# SilentStepStick-TMC2100_v12.net
KiCad netlist of a schematic drawn in EAGLE
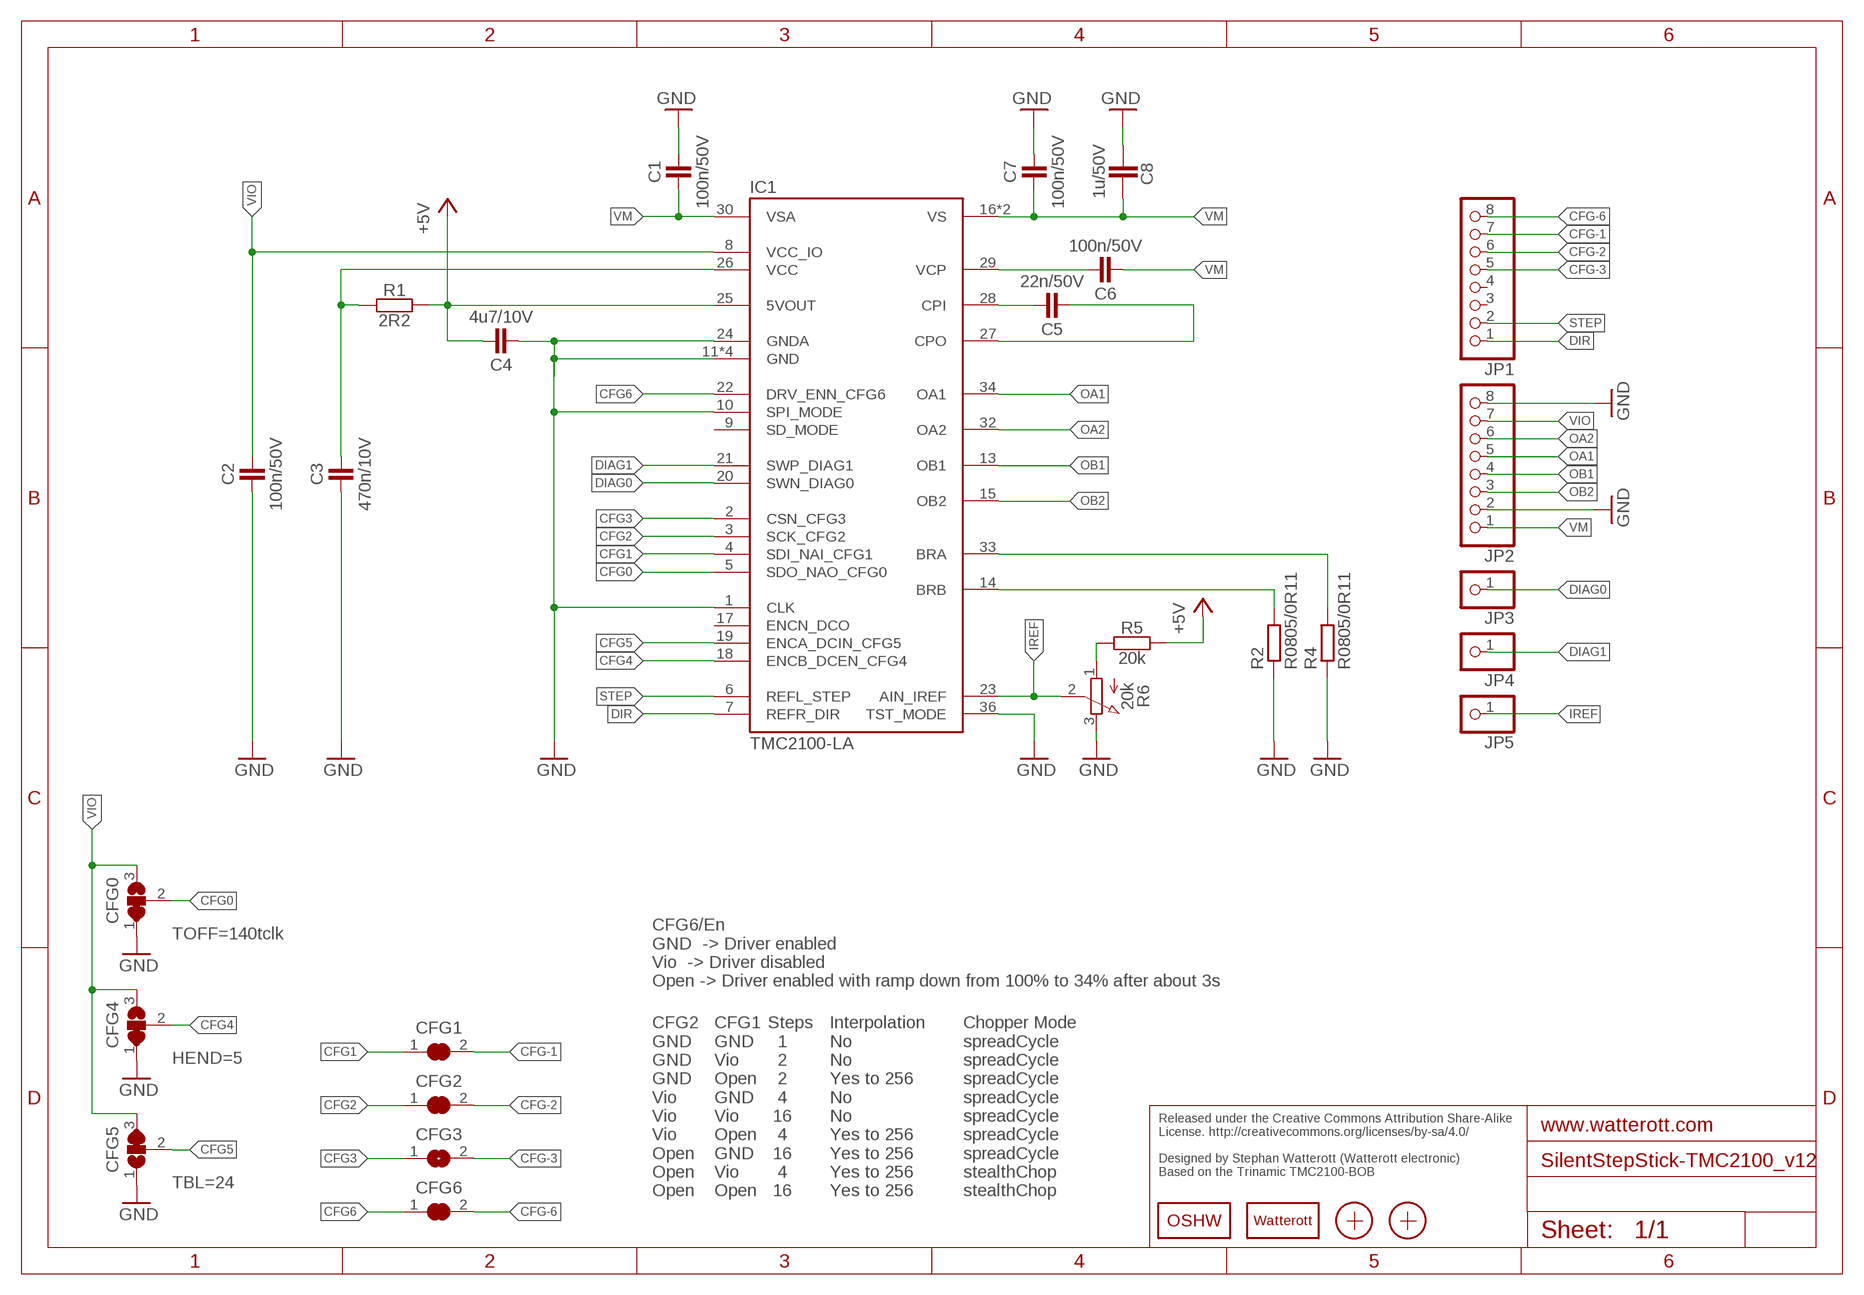
[diagram p0: schematic, sheet 1]

(export (version "E")
  (design (tool "Eeschema 10.0.6"))
  (components
    (comp (ref "C1")
      (value "100n/50V")
      (footprint "eagle-import:C0402")
      (libsource (lib "eagle-import") (part "CAPACITOR-0402"))
    )
    (comp (ref "C2")
      (value "100n/50V")
      (footprint "eagle-import:C0402")
      (libsource (lib "eagle-import") (part "CAPACITOR-0402"))
    )
    (comp (ref "C3")
      (value "470n/10V")
      (footprint "eagle-import:C0402")
      (libsource (lib "eagle-import") (part "CAPACITOR-0402"))
    )
    (comp (ref "C4")
      (value "4u7/10V")
      (footprint "eagle-import:C0402")
      (libsource (lib "eagle-import") (part "CAPACITOR-0402"))
    )
    (comp (ref "C5")
      (value "22n/50V")
      (footprint "eagle-import:C0402")
      (libsource (lib "eagle-import") (part "CAPACITOR-0402"))
    )
    (comp (ref "C6")
      (value "100n/50V")
      (footprint "eagle-import:C0402")
      (libsource (lib "eagle-import") (part "CAPACITOR-0402"))
    )
    (comp (ref "C7")
      (value "100n/50V")
      (footprint "eagle-import:C0402")
      (libsource (lib "eagle-import") (part "CAPACITOR-0402"))
    )
    (comp (ref "C8")
      (value "1u/50V")
      (footprint "eagle-import:C0603")
      (libsource (lib "eagle-import") (part "C-EUC0603"))
    )
    (comp (ref "CFG0")
      (value "JUMPER3-0201")
      (footprint "eagle-import:JUMPER3-0201")
      (libsource (lib "eagle-import") (part "JUMPER3-0201"))
    )
    (comp (ref "CFG1")
      (value "JUMPER2-0201")
      (footprint "eagle-import:JUMPER2-0201")
      (libsource (lib "eagle-import") (part "JUMPER2-0201"))
    )
    (comp (ref "CFG2")
      (value "JUMPER2-0201")
      (footprint "eagle-import:JUMPER2-0201")
      (libsource (lib "eagle-import") (part "JUMPER2-0201"))
    )
    (comp (ref "CFG3")
      (value "JUMPER2-0201")
      (footprint "eagle-import:JUMPER2-0201")
      (libsource (lib "eagle-import") (part "JUMPER2-0201"))
    )
    (comp (ref "CFG4")
      (value "JUMPER3-0201")
      (footprint "eagle-import:JUMPER3-0201")
      (libsource (lib "eagle-import") (part "JUMPER3-0201"))
    )
    (comp (ref "CFG5")
      (value "JUMPER3-0201")
      (footprint "eagle-import:JUMPER3-0201")
      (libsource (lib "eagle-import") (part "JUMPER3-0201"))
    )
    (comp (ref "CFG6")
      (value "JUMPER2-0201")
      (footprint "eagle-import:JUMPER2-0201")
      (libsource (lib "eagle-import") (part "JUMPER2-0201"))
    )
    (comp (ref "IC1")
      (value "TMC2100-LA")
      (footprint "eagle-import:QFN36-PAD")
      (libsource (lib "eagle-import") (part "TMC21X0-LA"))
    )
    (comp (ref "JP1")
      (value "PINHD-1X08_2.54-S")
      (footprint "eagle-import:1X08-S")
      (libsource (lib "eagle-import") (part "PINHD-1X08_2.54-S"))
    )
    (comp (ref "JP2")
      (value "PINHD-1X08_2.54-S")
      (footprint "eagle-import:1X08-S")
      (libsource (lib "eagle-import") (part "PINHD-1X08_2.54-S"))
    )
    (comp (ref "JP3")
      (value "PINHD-1X1")
      (footprint "eagle-import:1X01")
      (libsource (lib "eagle-import") (part "PINHD-1X1"))
    )
    (comp (ref "JP4")
      (value "PINHD-1X1")
      (footprint "eagle-import:1X01")
      (libsource (lib "eagle-import") (part "PINHD-1X1"))
    )
    (comp (ref "JP5")
      (value "PINHD-1X1")
      (footprint "eagle-import:1X01")
      (libsource (lib "eagle-import") (part "PINHD-1X1"))
    )
    (comp (ref "LOGO1")
      (value "OSHW_LOGOX0070")
      (footprint "eagle-import:OSHW_6X70")
      (libsource (lib "eagle-import") (part "OSHW_LOGOX0070"))
    )
    (comp (ref "LOGO2")
      (value "LOGO-S_PLACE_M")
      (footprint "eagle-import:SPARK_TPLACE_M")
      (libsource (lib "eagle-import") (part "LOGO-S_PLACE_M"))
    )
    (comp (ref "R1")
      (value "2R2")
      (footprint "eagle-import:C0402")
      (libsource (lib "eagle-import") (part "RESISTOR-0402"))
    )
    (comp (ref "R2")
      (value "R0805/0R11")
      (footprint "eagle-import:M0805")
      (libsource (lib "eagle-import") (part "R-EU_M0805"))
    )
    (comp (ref "R4")
      (value "R0805/0R11")
      (footprint "eagle-import:M0805")
      (libsource (lib "eagle-import") (part "R-EU_M0805"))
    )
    (comp (ref "R5")
      (value "20k")
      (footprint "eagle-import:C0402")
      (libsource (lib "eagle-import") (part "RESISTOR-0402"))
    )
    (comp (ref "R6")
      (value "20k")
      (footprint "eagle-import:POT_EVM3R")
      (libsource (lib "eagle-import") (part "POTEVM3R"))
    )
    (comp (ref "X1")
      (value "PASSER-07")
      (footprint "eagle-import:PASSER_07MM")
      (libsource (lib "eagle-import") (part "PASSER-07"))
    )
    (comp (ref "X2")
      (value "PASSER-07")
      (footprint "eagle-import:PASSER_07MM")
      (libsource (lib "eagle-import") (part "PASSER-07"))
    )
  )
  (nets
    (net (code "1") (name "+5V") (class "Default")
      (node (ref "C4") (pin "2") (pinfunction "2_2") (pintype "passive"))
      (node (ref "IC1") (pin "25") (pinfunction "5VOUT_25") (pintype "power_in"))
      (node (ref "R1") (pin "2") (pinfunction "2_2") (pintype "passive"))
      (node (ref "R5") (pin "2") (pinfunction "2_2") (pintype "passive"))
    )
    (net (code "2") (name "CFG-1") (class "Default")
      (node (ref "CFG1") (pin "2") (pinfunction "2_2") (pintype "passive"))
      (node (ref "JP1") (pin "7") (pinfunction "7_7") (pintype "passive"))
    )
    (net (code "3") (name "CFG-2") (class "Default")
      (node (ref "CFG2") (pin "2") (pinfunction "2_2") (pintype "passive"))
      (node (ref "JP1") (pin "6") (pinfunction "6_6") (pintype "passive"))
    )
    (net (code "4") (name "CFG-3") (class "Default")
      (node (ref "CFG3") (pin "2") (pinfunction "2_2") (pintype "passive"))
      (node (ref "JP1") (pin "5") (pinfunction "5_5") (pintype "passive"))
    )
    (net (code "5") (name "CFG-6") (class "Default")
      (node (ref "CFG6") (pin "2") (pinfunction "2_2") (pintype "passive"))
      (node (ref "JP1") (pin "8") (pinfunction "8_8") (pintype "passive"))
    )
    (net (code "6") (name "CFG0") (class "Default")
      (node (ref "CFG0") (pin "2") (pinfunction "2_2") (pintype "passive"))
      (node (ref "IC1") (pin "5") (pinfunction "SDO_NAO_CFG0_5") (pintype "bidirectional"))
    )
    (net (code "7") (name "CFG1") (class "Default")
      (node (ref "CFG1") (pin "1") (pinfunction "1_1") (pintype "passive"))
      (node (ref "IC1") (pin "4") (pinfunction "SDI_NAI_CFG1_4") (pintype "bidirectional"))
    )
    (net (code "8") (name "CFG2") (class "Default")
      (node (ref "CFG2") (pin "1") (pinfunction "1_1") (pintype "passive"))
      (node (ref "IC1") (pin "3") (pinfunction "SCK_CFG2_3") (pintype "bidirectional"))
    )
    (net (code "9") (name "CFG3") (class "Default")
      (node (ref "CFG3") (pin "1") (pinfunction "1_1") (pintype "passive"))
      (node (ref "IC1") (pin "2") (pinfunction "CSN_CFG3_2") (pintype "bidirectional"))
    )
    (net (code "10") (name "CFG4") (class "Default")
      (node (ref "CFG4") (pin "2") (pinfunction "2_2") (pintype "passive"))
      (node (ref "IC1") (pin "18") (pinfunction "ENCB_DCEN_CFG4_18") (pintype "bidirectional"))
    )
    (net (code "11") (name "CFG5") (class "Default")
      (node (ref "CFG5") (pin "2") (pinfunction "2_2") (pintype "passive"))
      (node (ref "IC1") (pin "19") (pinfunction "ENCA_DCIN_CFG5_19") (pintype "bidirectional"))
    )
    (net (code "12") (name "CFG6") (class "Default")
      (node (ref "CFG6") (pin "1") (pinfunction "1_1") (pintype "passive"))
      (node (ref "IC1") (pin "22") (pinfunction "DRV_ENN_CFG6_22") (pintype "bidirectional"))
    )
    (net (code "13") (name "DIAG0") (class "Default")
      (node (ref "IC1") (pin "20") (pinfunction "SWN_DIAG0_20") (pintype "bidirectional"))
      (node (ref "JP3") (pin "1") (pinfunction "1_1") (pintype "passive"))
    )
    (net (code "14") (name "DIAG1") (class "Default")
      (node (ref "IC1") (pin "21") (pinfunction "SWP_DIAG1_21") (pintype "bidirectional"))
      (node (ref "JP4") (pin "1") (pinfunction "1_1") (pintype "passive"))
    )
    (net (code "15") (name "DIR") (class "Default")
      (node (ref "IC1") (pin "7") (pinfunction "REFR_DIR_7") (pintype "bidirectional"))
      (node (ref "JP1") (pin "1") (pinfunction "1_1") (pintype "passive"))
    )
    (net (code "16") (name "GND") (class "Default")
      (node (ref "C1") (pin "2") (pinfunction "2_2") (pintype "passive"))
      (node (ref "C2") (pin "1") (pinfunction "1_1") (pintype "passive"))
      (node (ref "C3") (pin "1") (pinfunction "1_1") (pintype "passive"))
      (node (ref "C4") (pin "1") (pinfunction "1_1") (pintype "passive"))
      (node (ref "C7") (pin "2") (pinfunction "2_2") (pintype "passive"))
      (node (ref "C8") (pin "2") (pinfunction "2_2") (pintype "passive"))
      (node (ref "CFG0") (pin "1") (pinfunction "1_1") (pintype "passive"))
      (node (ref "CFG4") (pin "1") (pinfunction "1_1") (pintype "passive"))
      (node (ref "CFG5") (pin "1") (pinfunction "1_1") (pintype "passive"))
      (node (ref "IC1") (pin "1") (pinfunction "CLK_1") (pintype "bidirectional"))
      (node (ref "IC1") (pin "10") (pinfunction "SPI_MODE_10") (pintype "bidirectional"))
      (node (ref "IC1") (pin "11") (pinfunction "GND_11") (pintype "power_in"))
      (node (ref "IC1") (pin "12") (pinfunction "GND_12") (pintype "power_in"))
      (node (ref "IC1") (pin "24") (pinfunction "GNDA_24") (pintype "power_in"))
      (node (ref "IC1") (pin "35") (pinfunction "GND_35") (pintype "power_in"))
      (node (ref "IC1") (pin "36") (pinfunction "TST_MODE_36") (pintype "bidirectional"))
      (node (ref "IC1") (pin "TP") (pinfunction "GND_TP") (pintype "power_in"))
      (node (ref "JP2") (pin "2") (pinfunction "2_2") (pintype "passive"))
      (node (ref "JP2") (pin "8") (pinfunction "8_8") (pintype "passive"))
      (node (ref "R2") (pin "1") (pinfunction "1_1") (pintype "passive"))
      (node (ref "R4") (pin "1") (pinfunction "1_1") (pintype "passive"))
      (node (ref "R6") (pin "3") (pinfunction "E_3") (pintype "passive"))
    )
    (net (code "17") (name "IREF") (class "Default")
      (node (ref "IC1") (pin "23") (pinfunction "AIN_IREF_23") (pintype "passive"))
      (node (ref "JP5") (pin "1") (pinfunction "1_1") (pintype "passive"))
      (node (ref "R6") (pin "2") (pinfunction "S_2") (pintype "passive"))
    )
    (net (code "18") (name "Net-(IC1-BRA)") (class "Default")
      (node (ref "IC1") (pin "33") (pinfunction "BRA_33") (pintype "output"))
      (node (ref "R4") (pin "2") (pinfunction "2_2") (pintype "passive"))
    )
    (net (code "19") (name "Net-(IC1-BRB)") (class "Default")
      (node (ref "IC1") (pin "14") (pinfunction "BRB_14") (pintype "output"))
      (node (ref "R2") (pin "2") (pinfunction "2_2") (pintype "passive"))
    )
    (net (code "20") (name "Net-(IC1-CPI)") (class "Default")
      (node (ref "C5") (pin "2") (pinfunction "2_2") (pintype "passive"))
      (node (ref "IC1") (pin "28") (pinfunction "CPI_28") (pintype "passive"))
    )
    (net (code "21") (name "Net-(IC1-CPO)") (class "Default")
      (node (ref "C5") (pin "1") (pinfunction "1_1") (pintype "passive"))
      (node (ref "IC1") (pin "27") (pinfunction "CPO_27") (pintype "passive"))
    )
    (net (code "22") (name "Net-(IC1-VCC)") (class "Default")
      (node (ref "C3") (pin "2") (pinfunction "2_2") (pintype "passive"))
      (node (ref "IC1") (pin "26") (pinfunction "VCC_26") (pintype "power_in"))
      (node (ref "R1") (pin "1") (pinfunction "1_1") (pintype "passive"))
    )
    (net (code "23") (name "Net-(IC1-VCP)") (class "Default")
      (node (ref "C6") (pin "2") (pinfunction "2_2") (pintype "passive"))
      (node (ref "IC1") (pin "29") (pinfunction "VCP_29") (pintype "passive"))
    )
    (net (code "24") (name "Net-(R6-A)") (class "Default")
      (node (ref "R5") (pin "1") (pinfunction "1_1") (pintype "passive"))
      (node (ref "R6") (pin "1") (pinfunction "A_1") (pintype "passive"))
    )
    (net (code "25") (name "OA1") (class "Default")
      (node (ref "IC1") (pin "34") (pinfunction "OA1_34") (pintype "output"))
      (node (ref "JP2") (pin "5") (pinfunction "5_5") (pintype "passive"))
    )
    (net (code "26") (name "OA2") (class "Default")
      (node (ref "IC1") (pin "32") (pinfunction "OA2_32") (pintype "output"))
      (node (ref "JP2") (pin "6") (pinfunction "6_6") (pintype "passive"))
    )
    (net (code "27") (name "OB1") (class "Default")
      (node (ref "IC1") (pin "13") (pinfunction "OB1_13") (pintype "output"))
      (node (ref "JP2") (pin "4") (pinfunction "4_4") (pintype "passive"))
    )
    (net (code "28") (name "OB2") (class "Default")
      (node (ref "IC1") (pin "15") (pinfunction "OB2_15") (pintype "output"))
      (node (ref "JP2") (pin "3") (pinfunction "3_3") (pintype "passive"))
    )
    (net (code "29") (name "STEP") (class "Default")
      (node (ref "IC1") (pin "6") (pinfunction "REFL_STEP_6") (pintype "bidirectional"))
      (node (ref "JP1") (pin "2") (pinfunction "2_2") (pintype "passive"))
    )
    (net (code "30") (name "VIO") (class "Default")
      (node (ref "C2") (pin "2") (pinfunction "2_2") (pintype "passive"))
      (node (ref "CFG0") (pin "3") (pinfunction "3_3") (pintype "passive"))
      (node (ref "CFG4") (pin "3") (pinfunction "3_3") (pintype "passive"))
      (node (ref "CFG5") (pin "3") (pinfunction "3_3") (pintype "passive"))
      (node (ref "IC1") (pin "8") (pinfunction "VCC_IO_8") (pintype "power_in"))
      (node (ref "JP2") (pin "7") (pinfunction "7_7") (pintype "passive"))
    )
    (net (code "31") (name "VM") (class "Default")
      (node (ref "C1") (pin "1") (pinfunction "1_1") (pintype "passive"))
      (node (ref "C6") (pin "1") (pinfunction "1_1") (pintype "passive"))
      (node (ref "C7") (pin "1") (pinfunction "1_1") (pintype "passive"))
      (node (ref "C8") (pin "1") (pinfunction "1_1") (pintype "passive"))
      (node (ref "IC1") (pin "16") (pinfunction "VS_16") (pintype "power_in"))
      (node (ref "IC1") (pin "30") (pinfunction "VSA_30") (pintype "power_in"))
      (node (ref "IC1") (pin "31") (pinfunction "VS_31") (pintype "power_in"))
      (node (ref "JP2") (pin "1") (pinfunction "1_1") (pintype "passive"))
    )
    (net (code "32") (name "unconnected-(IC1-ENCN_DCO-Pad17)") (class "Default")
      (node (ref "IC1") (pin "17") (pinfunction "ENCN_DCO_17") (pintype "bidirectional"))
    )
    (net (code "33") (name "unconnected-(IC1-SD_MODE-Pad9)") (class "Default")
      (node (ref "IC1") (pin "9") (pinfunction "SD_MODE_9") (pintype "bidirectional"))
    )
    (net (code "34") (name "unconnected-(JP1-Pad3)") (class "Default")
      (node (ref "JP1") (pin "3") (pinfunction "3_3") (pintype "passive"))
    )
    (net (code "35") (name "unconnected-(JP1-Pad4)") (class "Default")
      (node (ref "JP1") (pin "4") (pinfunction "4_4") (pintype "passive"))
    )
  )
)
